# Motor_Power_Switch.net
KiCad netlist of a schematic drawn in Altium Designer
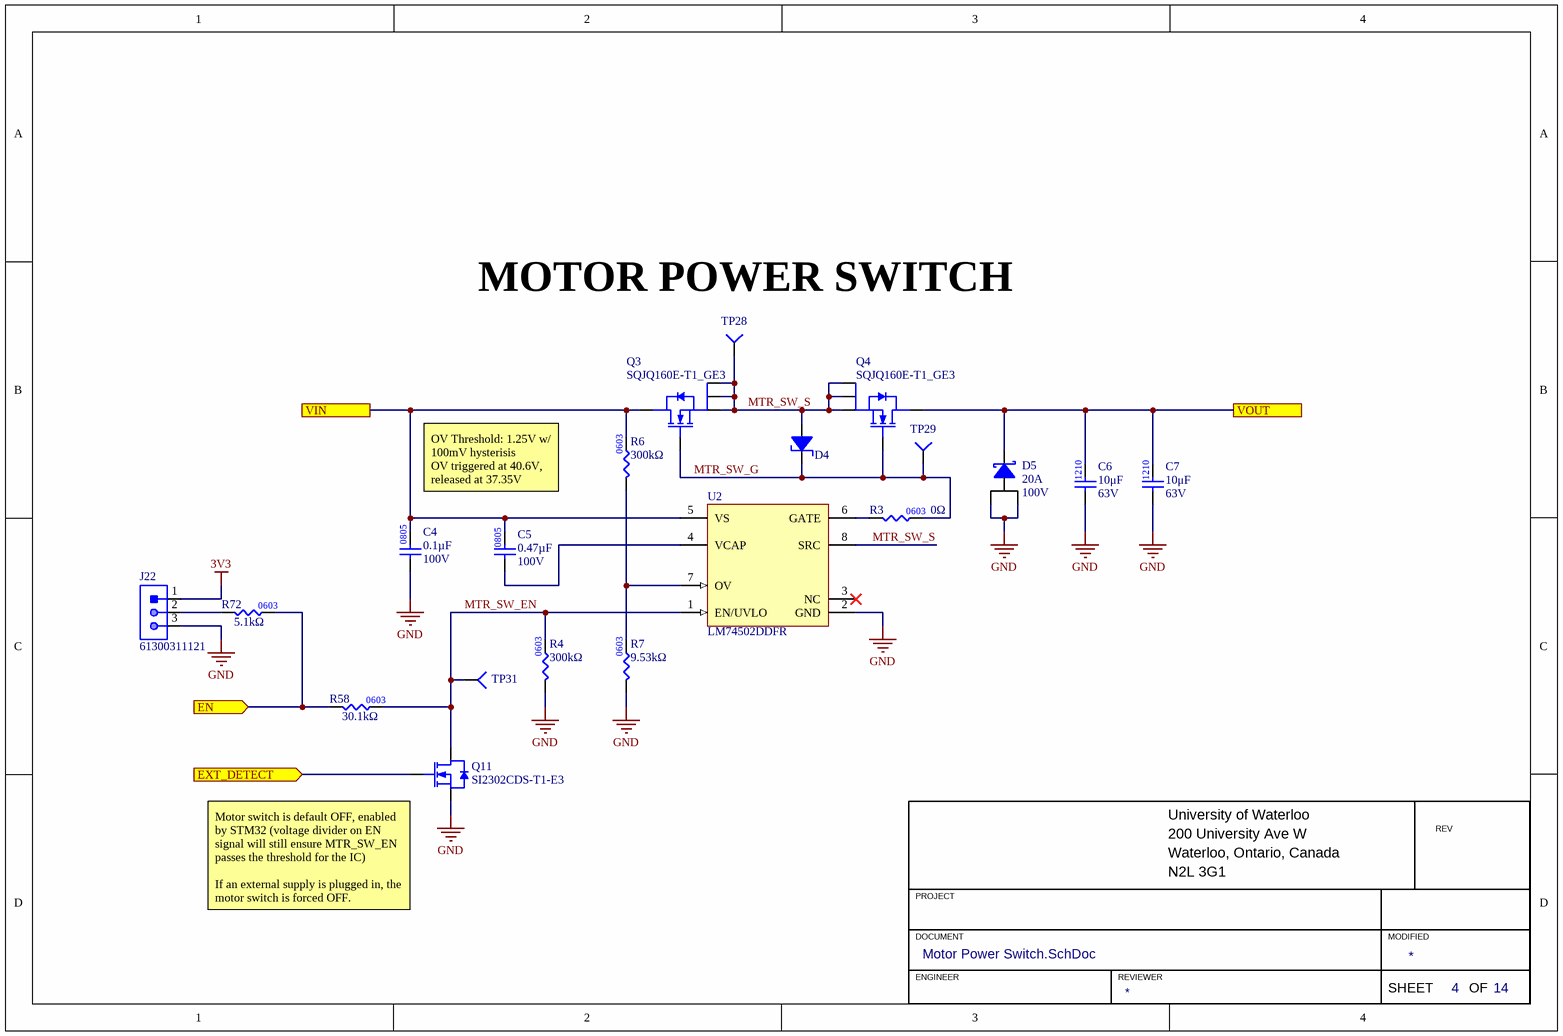
[diagram p0: Motor Power Switch.SchDoc]

(export (version "E")
  (design (tool "Eeschema 10.0.6"))
  (components
    (comp (ref "C4")
      (value "0.1µF")
      (footprint "CAP0805")
      (description "CAP CER 0.1UF 100V X7R 0805")
      (fields (field (name "VOLTAGE RATING") "100V") (field (name "Comment") "CAP_0.1uF_100V_0805"))
      (libsource (lib "Personal_Schematic_Library_2022") (part "CAP_0.1uF_100V_0805"))
    )
    (comp (ref "C5")
      (value "0.47µF")
      (footprint "CAP0805")
      (description "CAP CER 0.47UF 100V X7R 0805")
      (fields (field (name "VOLTAGE RATING") "100V") (field (name "Comment") "CAP_0.47uF_100V_0805"))
      (libsource (lib "Personal_Schematic_Library_2022") (part "CAP_0.47uF_100V_0805"))
    )
    (comp (ref "C6")
      (value "10μF")
      (footprint "CAP1210")
      (description "CAP CER 10UF 63V X7R 1210")
      (fields (field (name "VOLTAGE RATING") "63V") (field (name "Comment") "CAP_10uF_63V_1210"))
      (libsource (lib "Personal_Schematic_Library_2022") (part "CAP_10uF_63V_1210"))
    )
    (comp (ref "C7")
      (value "10μF")
      (footprint "CAP1210")
      (description "CAP CER 10UF 63V X7R 1210")
      (fields (field (name "VOLTAGE RATING") "63V") (field (name "Comment") "CAP_10uF_63V_1210"))
      (libsource (lib "Personal_Schematic_Library_2022") (part "CAP_10uF_63V_1210"))
    )
    (comp (ref "D4")
      (value "DIO_ZENER_16V")
      (footprint "SOD-123_FLAT")
      (description "DIODE ZENER 16V 500MW SOD123")
      (libsource (lib "Personal_Schematic_Library_2022") (part "DIO_ZENER_16V"))
    )
    (comp (ref "D5")
      (value "DIO_SCHOTTKY_100V_20A")
      (footprint "D-PAK")
      (description "100V, 20A, DPAK, DIODE SCHOTTKY")
      (fields (field (name "CURRENT - AVERAGE RECTIFIED (IO)") "20A") (field (name "VR (MAX)") "100V"))
      (libsource (lib "Personal_Schematic_Library_2022") (part "DIO_SCHOTTKY_100V_20A"))
    )
    (comp (ref "J22")
      (value "HEADER 3x1")
      (footprint "HDR1X3")
      (description "CONN HEADER VERT 3POS 2.54MM")
      (fields (field (name "MANUFACTURER PART NUMBER 1") "61300311121"))
      (libsource (lib "Personal_Schematic_Library_2022") (part "HEADER 3x1"))
    )
    (comp (ref "Q3")
      (value "NMOS_60V_603A")
      (footprint "VISHAY_PowerPAK-8x8")
      (description "AUTOMOTIVE N-CHANNEL 60 V (D-S)")
      (fields (field (name "MANUFACTURER PART NUMBER 1") "SQJQ160E-T1_GE3"))
      (libsource (lib "Personal_Schematic_Library_2022") (part "NMOS_60V_603A"))
    )
    (comp (ref "Q4")
      (value "NMOS_60V_603A")
      (footprint "VISHAY_PowerPAK-8x8")
      (description "AUTOMOTIVE N-CHANNEL 60 V (D-S)")
      (fields (field (name "MANUFACTURER PART NUMBER 1") "SQJQ160E-T1_GE3"))
      (libsource (lib "Personal_Schematic_Library_2022") (part "NMOS_60V_603A"))
    )
    (comp (ref "Q11")
      (value "NMOS_20V_6A")
      (footprint "SOT23-3")
      (description "MOSFET N-CH 20V 2.6A SOT23-3")
      (fields (field (name "MANUFACTURER PART NUMBER 1") "SI2302CDS-T1-E3"))
      (libsource (lib "Personal_Schematic_Library_2022") (part "NMOS_20V_2.6A"))
    )
    (comp (ref "R3")
      (value "0Ω")
      (footprint "RES0603")
      (description "RES 0 OHM JUMPER 1/10W 0603")
      (fields (field (name "Comment") "RES_0Ω_0603"))
      (libsource (lib "Personal_Schematic_Library_2022") (part "RES_0Ω_0603"))
    )
    (comp (ref "R4")
      (value "300kΩ")
      (footprint "RES0603")
      (description "RES 300K OHM 1% 1/10W 0603")
      (fields (field (name "TOLERANCE") "1%") (field (name "Comment") "RES_300kΩ_0603_1%"))
      (libsource (lib "Personal_Schematic_Library_2022") (part "RES_300kΩ_0603_1%"))
    )
    (comp (ref "R6")
      (value "300kΩ")
      (footprint "RES0603")
      (description "RES 300K OHM 1% 1/10W 0603")
      (fields (field (name "TOLERANCE") "1%") (field (name "Comment") "RES_300kΩ_0603_1%"))
      (libsource (lib "Personal_Schematic_Library_2022") (part "RES_300kΩ_0603_1%"))
    )
    (comp (ref "R7")
      (value "9.53kΩ")
      (footprint "RES0603")
      (description "RES 9.53K OHM 1% 1/10W 0603")
      (fields (field (name "Comment") "RES_9.53kΩ_0603_1%"))
      (libsource (lib "Personal_Schematic_Library_2022") (part "RES_9.53kΩ_0603_1%"))
    )
    (comp (ref "R58")
      (value "30.1kΩ")
      (footprint "RES0603")
      (description "RES 30.1K OHM 1% 1/10W 0603")
      (fields (field (name "Comment") "RES_30.1kΩ_0603_1%"))
      (libsource (lib "Personal_Schematic_Library_2022") (part "RES_30.1kΩ_0603_1%"))
    )
    (comp (ref "R72")
      (value "5.1kΩ")
      (footprint "RES0603")
      (description "RES 5.1K OHM 1% 1/10W 0603")
      (fields (field (name "Comment") "RES_5.1kΩ_0603_1%"))
      (libsource (lib "Personal_Schematic_Library_2022") (part "RES_5.1kΩ_0603_1%"))
    )
    (comp (ref "TP28")
      (value "TESTPOINT_1MM_SQUARE")
      (footprint "TESTPOINT_SQUARE_1MM")
      (description "TESTPOINT 1MM SQUARE")
      (libsource (lib "Personal_Schematic_Library_2022") (part "TESTPOINT_1MM_SQUARE"))
    )
    (comp (ref "TP29")
      (value "TESTPOINT_1MM_CIRCLE")
      (footprint "TESTPOINT_CIRCLE_1MM")
      (description "TESTPOINT 1MM CIRCLE")
      (libsource (lib "Personal_Schematic_Library_2022") (part "TESTPOINT_1MM_CIRCLE"))
    )
    (comp (ref "TP31")
      (value "TESTPOINT_1MM_CIRCLE")
      (footprint "TESTPOINT_CIRCLE_1MM")
      (description "TESTPOINT 1MM CIRCLE")
      (libsource (lib "Personal_Schematic_Library_2022") (part "TESTPOINT_1MM_CIRCLE"))
    )
    (comp (ref "U2")
      (value "LM74502DDFR")
      (footprint "TI_SOT23-8")
      (description "3.2-V TO 65-V INDUSTRIAL RPP CON")
      (libsource (lib "Personal_Schematic_Library_2022") (part "LM74502DDFR"))
    )
  )
  (nets
    (net (code "1") (name "/EN") (class "Default")
      (node (ref "R58") (pin "1") (pinfunction "1_1") (pintype "passive"))
      (node (ref "R72") (pin "2") (pinfunction "2_2") (pintype "passive"))
    )
    (net (code "2") (name "/EXT_DETECT") (class "Default")
      (node (ref "Q11") (pin "1") (pinfunction "GATE_1") (pintype "passive"))
    )
    (net (code "3") (name "/MTR_SW_EN") (class "Default")
      (node (ref "Q11") (pin "3") (pinfunction "DRAIN_3") (pintype "passive"))
      (node (ref "R4") (pin "2") (pinfunction "2_2") (pintype "passive"))
      (node (ref "R58") (pin "2") (pinfunction "2_2") (pintype "passive"))
      (node (ref "TP31") (pin "1") (pinfunction "=value_1") (pintype "passive"))
      (node (ref "U2") (pin "1") (pinfunction "EN/UVLO_1") (pintype "input"))
    )
    (net (code "4") (name "/MTR_SW_G") (class "Default")
      (node (ref "D4") (pin "2") (pinfunction "Cathode_2") (pintype "passive"))
      (node (ref "Q3") (pin "1") (pinfunction "Gate_1") (pintype "passive"))
      (node (ref "Q4") (pin "1") (pinfunction "Gate_1") (pintype "passive"))
      (node (ref "R3") (pin "2") (pinfunction "2_2") (pintype "passive"))
      (node (ref "TP29") (pin "1") (pinfunction "=value_1") (pintype "passive"))
    )
    (net (code "5") (name "/MTR_SW_S") (class "Default")
      (node (ref "D4") (pin "1") (pinfunction "Anode_1") (pintype "passive"))
      (node (ref "Q3") (pin "2") (pinfunction "Source_2") (pintype "passive"))
      (node (ref "Q3") (pin "3") (pinfunction "Source_3") (pintype "passive"))
      (node (ref "Q3") (pin "4") (pinfunction "Source_4") (pintype "passive"))
      (node (ref "Q4") (pin "2") (pinfunction "Source_2") (pintype "passive"))
      (node (ref "Q4") (pin "3") (pinfunction "Source_3") (pintype "passive"))
      (node (ref "Q4") (pin "4") (pinfunction "Source_4") (pintype "passive"))
      (node (ref "TP28") (pin "1") (pinfunction "=value_1") (pintype "passive"))
      (node (ref "U2") (pin "8") (pinfunction "SRC_8") (pintype "power_in"))
    )
    (net (code "6") (name "/VIN") (class "Default")
      (node (ref "C4") (pin "2") (pinfunction "2_2") (pintype "passive"))
      (node (ref "C5") (pin "2") (pinfunction "2_2") (pintype "passive"))
      (node (ref "Q3") (pin "5") (pinfunction "Drain_5") (pintype "passive"))
      (node (ref "R6") (pin "2") (pinfunction "2_2") (pintype "passive"))
      (node (ref "U2") (pin "5") (pinfunction "VS_5") (pintype "power_in"))
    )
    (net (code "7") (name "/VOUT") (class "Default")
      (node (ref "C6") (pin "2") (pinfunction "2_2") (pintype "passive"))
      (node (ref "C7") (pin "2") (pinfunction "2_2") (pintype "passive"))
      (node (ref "D5") (pin "1") (pinfunction "Cathode_1") (pintype "passive"))
      (node (ref "Q4") (pin "5") (pinfunction "Drain_5") (pintype "passive"))
    )
    (net (code "8") (name "3V3") (class "Default")
      (node (ref "J22") (pin "1") (pinfunction "1_1") (pintype "passive"))
    )
    (net (code "9") (name "GND") (class "Default")
      (node (ref "C4") (pin "1") (pinfunction "1_1") (pintype "passive"))
      (node (ref "C6") (pin "1") (pinfunction "1_1") (pintype "passive"))
      (node (ref "C7") (pin "1") (pinfunction "1_1") (pintype "passive"))
      (node (ref "D5") (pin "2") (pinfunction "Anode_2") (pintype "passive"))
      (node (ref "D5") (pin "3") (pinfunction "Anode_3") (pintype "passive"))
      (node (ref "J22") (pin "3") (pinfunction "3_3") (pintype "passive"))
      (node (ref "Q11") (pin "2") (pinfunction "SOURCE_2") (pintype "passive"))
      (node (ref "R4") (pin "1") (pinfunction "1_1") (pintype "passive"))
      (node (ref "R7") (pin "1") (pinfunction "1_1") (pintype "passive"))
      (node (ref "U2") (pin "2") (pinfunction "GND_2") (pintype "power_in"))
    )
    (net (code "10") (name "Net-(J22-Pad2)") (class "Default")
      (node (ref "J22") (pin "2") (pinfunction "2_2") (pintype "passive"))
      (node (ref "R72") (pin "1") (pinfunction "1_1") (pintype "passive"))
    )
    (net (code "11") (name "Net-(U2-GATE)") (class "Default")
      (node (ref "R3") (pin "1") (pinfunction "1_1") (pintype "passive"))
      (node (ref "U2") (pin "6") (pinfunction "GATE_6") (pintype "power_in"))
    )
    (net (code "12") (name "Net-(U2-OV)") (class "Default")
      (node (ref "R6") (pin "1") (pinfunction "1_1") (pintype "passive"))
      (node (ref "R7") (pin "2") (pinfunction "2_2") (pintype "passive"))
      (node (ref "U2") (pin "7") (pinfunction "OV_7") (pintype "input"))
    )
    (net (code "13") (name "Net-(U2-VCAP)") (class "Default")
      (node (ref "C5") (pin "1") (pinfunction "1_1") (pintype "passive"))
      (node (ref "U2") (pin "4") (pinfunction "VCAP_4") (pintype "power_in"))
    )
    (net (code "14") (name "unconnected-(U2-NC-Pad3)") (class "Default")
      (node (ref "U2") (pin "3") (pinfunction "NC_3") (pintype "passive+no_connect"))
    )
  )
)
